# ESP32_School_Prototype.net
KiCad netlist of a schematic drawn in EAGLE
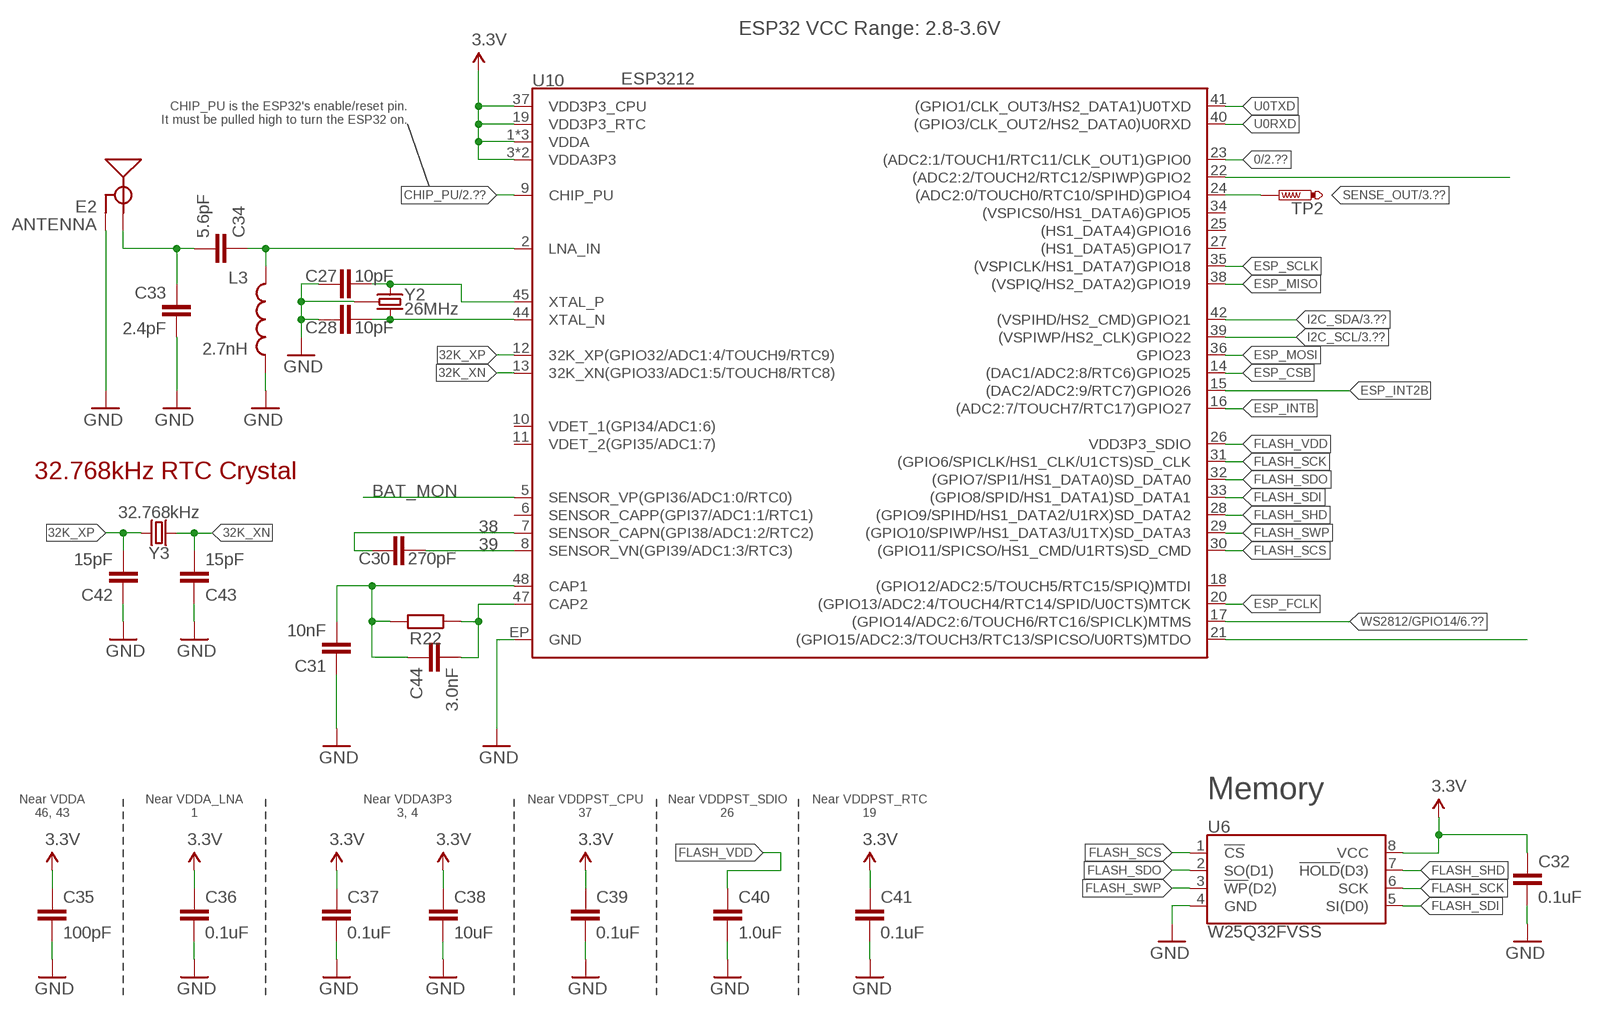
[diagram p0: schematic, sheet 1]
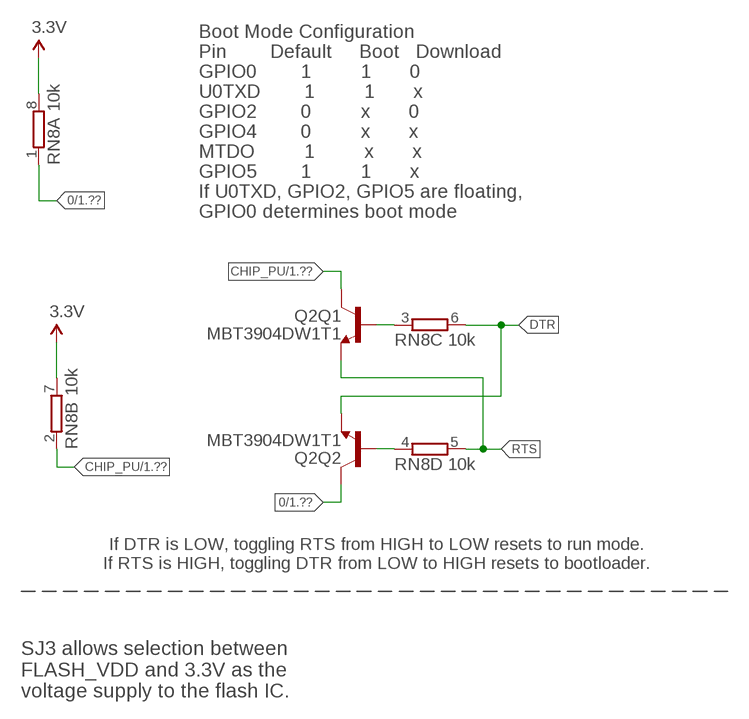
[diagram p1: schematic, sheet 2]
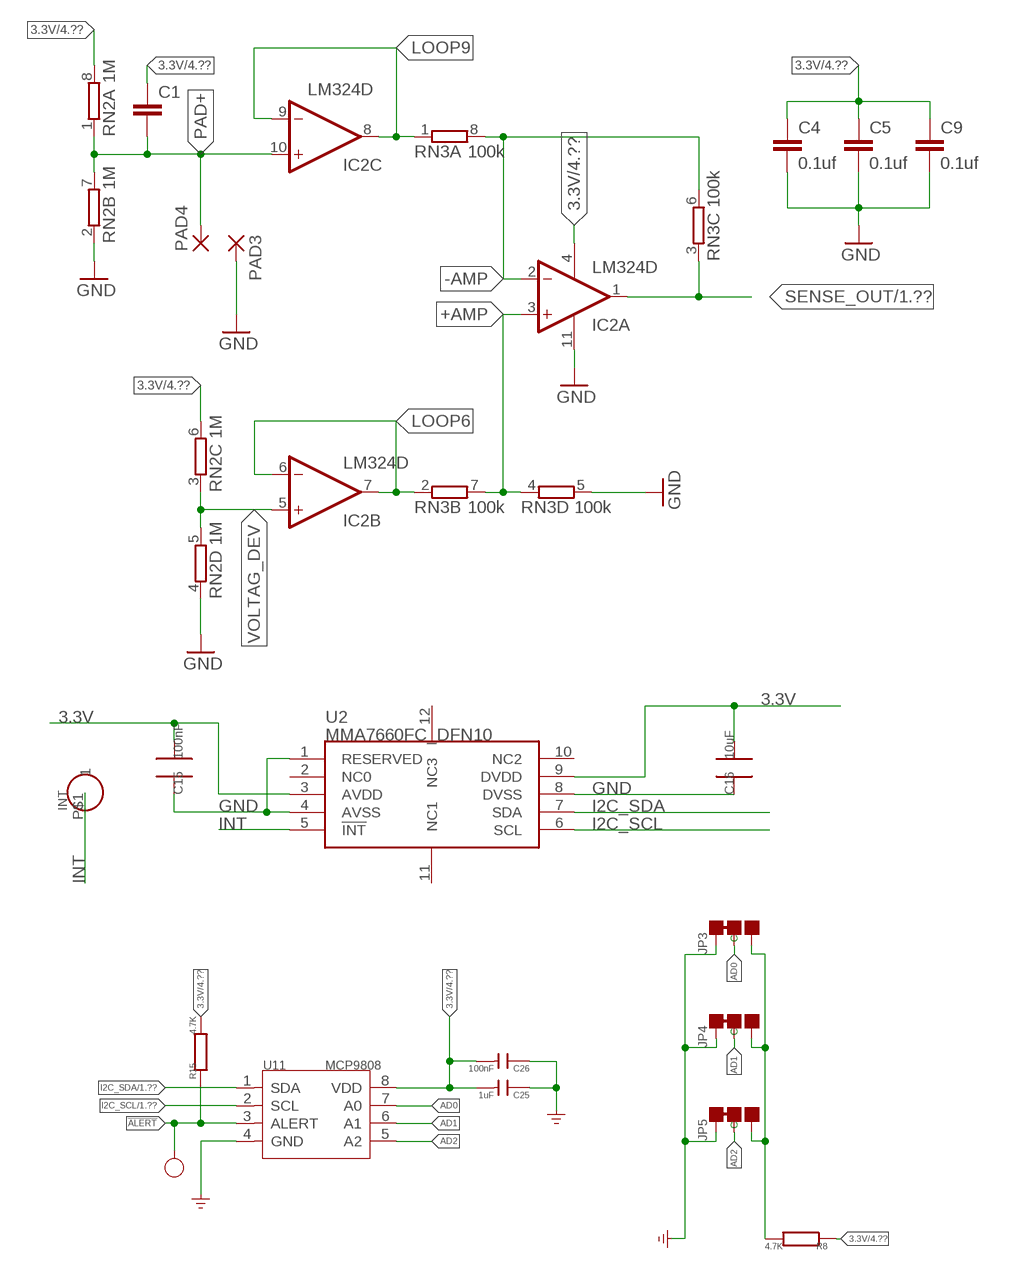
[diagram p2: schematic, sheet 3]
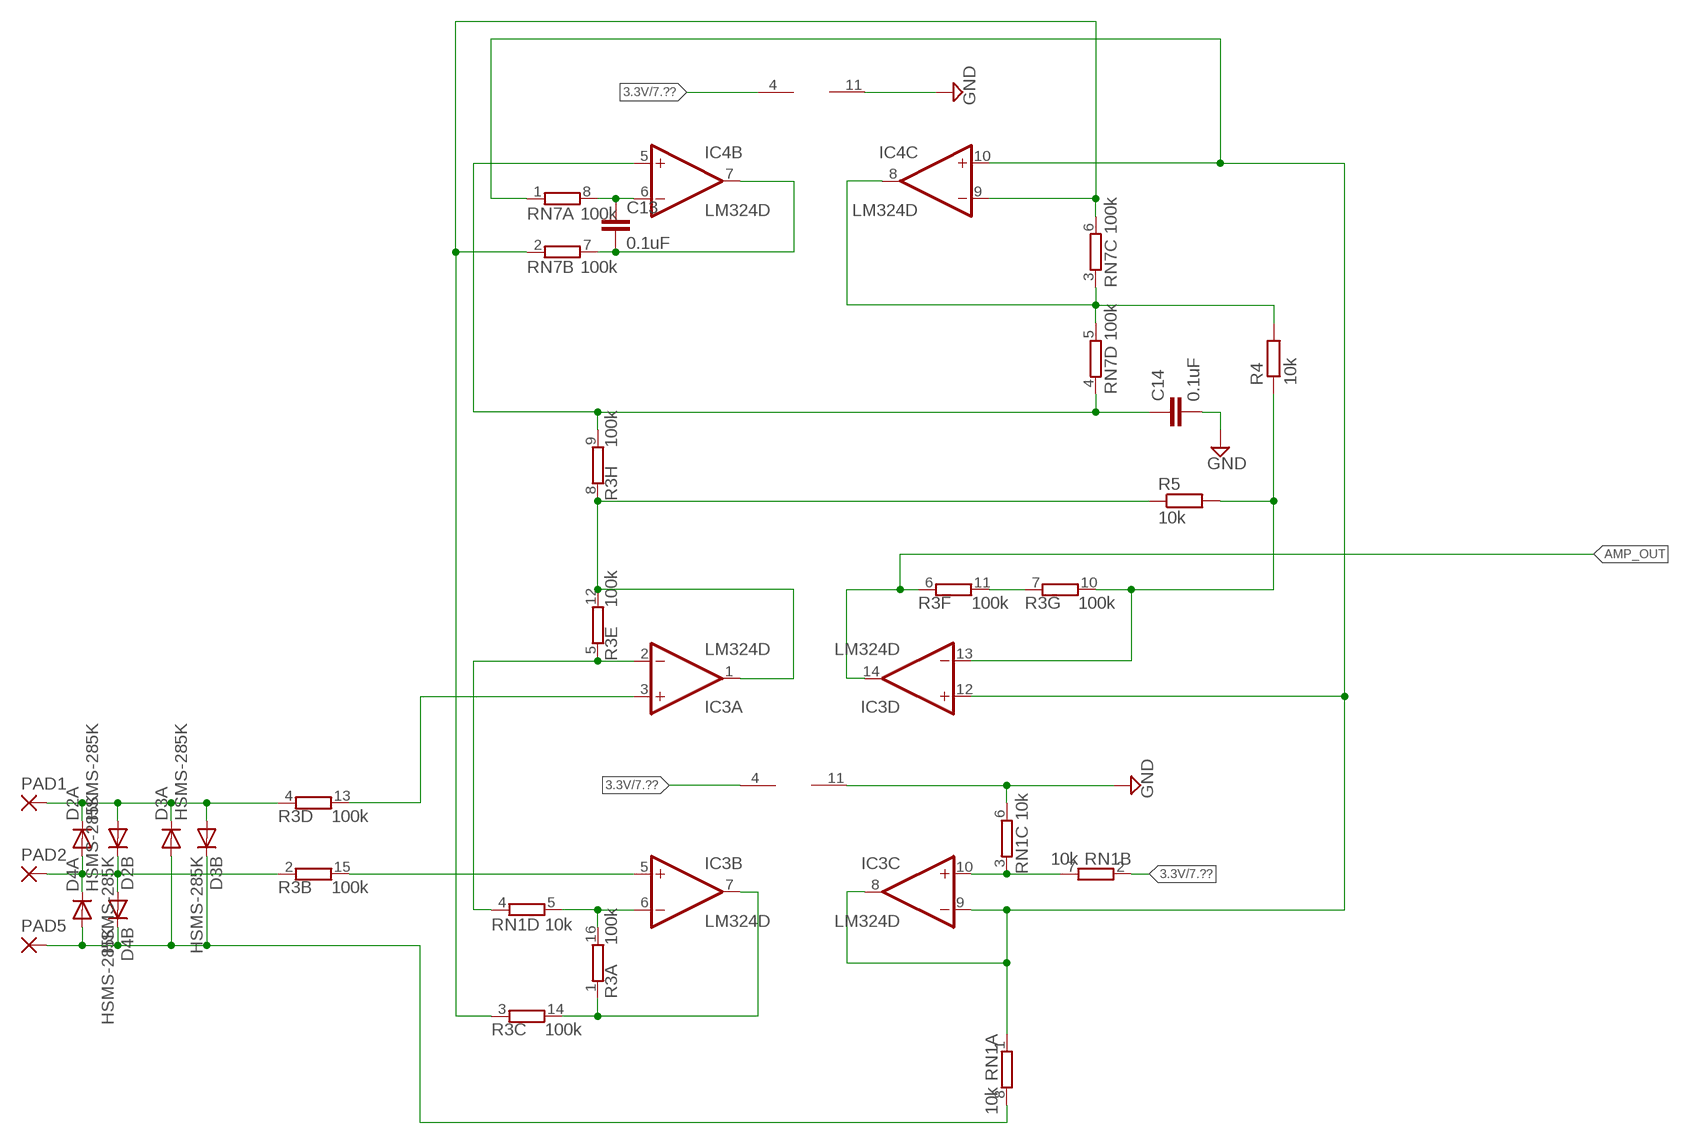
[diagram p3: schematic, sheet 4]
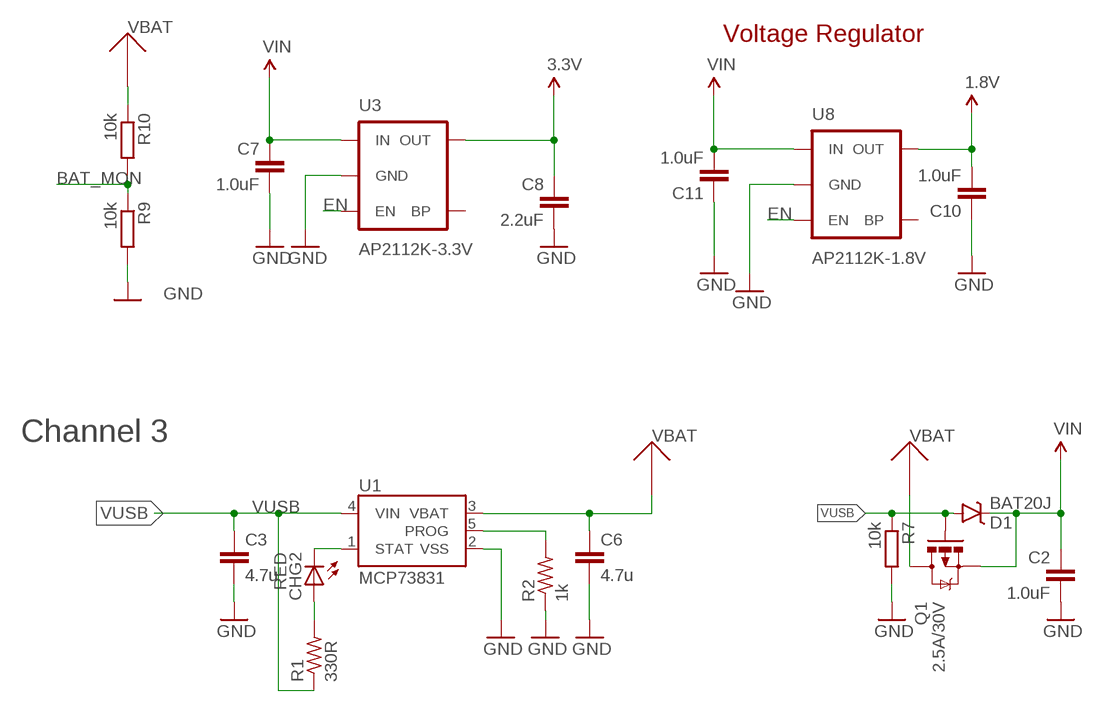
[diagram p4: schematic, sheet 5]
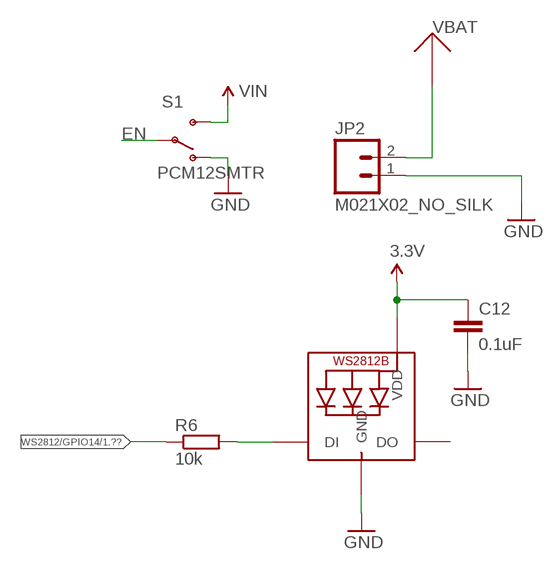
[diagram p5: schematic, sheet 6]
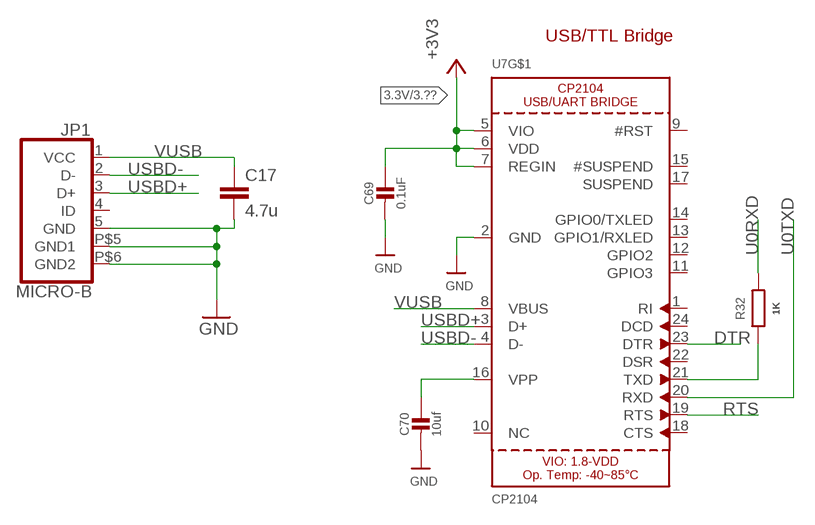
[diagram p6: schematic, sheet 7]
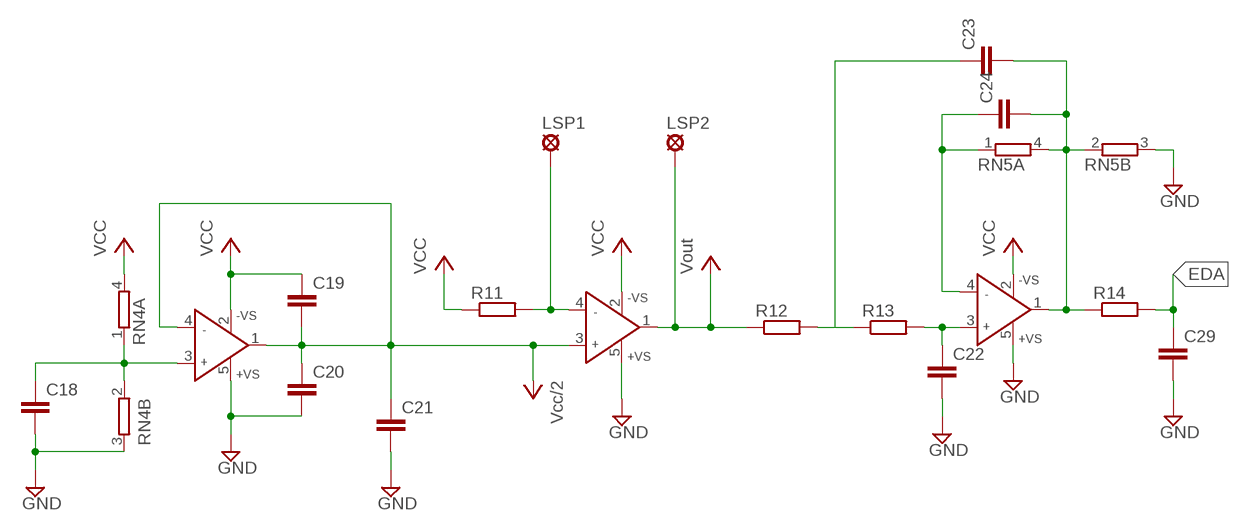
[diagram p7: schematic, sheet 8]

(export (version "E")
  (design (tool "Eeschema 10.0.6"))
  (components
    (comp (ref "C1")
      (value "C-EUC0603K")
      (footprint "eagle-import:C0603K")
      (libsource (lib "eagle-import") (part "rcl_334_C-EUC0603K"))
    )
    (comp (ref "C4")
      (value "0.1uf")
      (footprint "eagle-import:C0603K")
      (libsource (lib "eagle-import") (part "rcl_334_C-EUC0603K"))
    )
    (comp (ref "C5")
      (value "0.1uf")
      (footprint "eagle-import:C0603K")
      (libsource (lib "eagle-import") (part "rcl_334_C-EUC0603K"))
    )
    (comp (ref "C9")
      (value "0.1uf")
      (footprint "eagle-import:C0603K")
      (libsource (lib "eagle-import") (part "rcl_334_C-EUC0603K"))
    )
    (comp (ref "C15")
      (value "100nF")
      (footprint "eagle-import:0603_S")
      (libsource (lib "eagle-import") (part "C0603_S"))
    )
    (comp (ref "C16")
      (value "10uF")
      (footprint "eagle-import:0805_S")
      (libsource (lib "eagle-import") (part "C0805_S"))
    )
    (comp (ref "C25")
      (value "1uF")
      (footprint "eagle-import:C0603")
      (libsource (lib "eagle-import") (part "C-0603"))
    )
    (comp (ref "C26")
      (value "100nF")
      (footprint "eagle-import:C0603")
      (libsource (lib "eagle-import") (part "C-0603"))
    )
    (comp (ref "GND16")
      (value "TEST-POINT'4545'")
      (footprint "eagle-import:TP-D45MIL")
      (fields (field (name "PARTNO") "DNP"))
      (libsource (lib "eagle-import") (part "TEST-POINT'4545'"))
    )
    (comp (ref "IC2")
      (value "LM324D")
      (footprint "eagle-import:SO14")
      (libsource (lib "eagle-import") (part "LM324D"))
    )
    (comp (ref "INT")
      (value "HEADER-1P-35")
      (footprint "eagle-import:1P-65_35MIL")
      (libsource (lib "eagle-import") (part "HEADER-1P-35"))
    )
    (comp (ref "JP3")
      (value "JP-3P-SHORT")
      (footprint "eagle-import:3P-SMD-SHORT")
      (libsource (lib "eagle-import") (part "JP-3P-SHORT"))
    )
    (comp (ref "JP4")
      (value "JP-3P-SHORT")
      (footprint "eagle-import:3P-SMD-SHORT")
      (libsource (lib "eagle-import") (part "JP-3P-SHORT"))
    )
    (comp (ref "JP5")
      (value "JP-3P-SHORT")
      (footprint "eagle-import:3P-SMD-SHORT")
      (libsource (lib "eagle-import") (part "JP-3P-SHORT"))
    )
    (comp (ref "PAD3")
      (value "2,54/1,1")
      (footprint "eagle-import:2,54_1,1")
      (libsource (lib "eagle-import") (part "2,54/1,1"))
    )
    (comp (ref "PAD4")
      (value "2,54/1,1")
      (footprint "eagle-import:2,54_1,1")
      (libsource (lib "eagle-import") (part "2,54/1,1"))
    )
    (comp (ref "R8")
      (value "4.7K")
      (footprint "eagle-import:R0402")
      (libsource (lib "eagle-import") (part "resistor_348_R-EU_R0402"))
    )
    (comp (ref "R15")
      (value "4.7K")
      (footprint "eagle-import:R0402")
      (libsource (lib "eagle-import") (part "resistor_348_R-EU_R0402"))
    )
    (comp (ref "RN2")
      (value "1M")
      (footprint "eagle-import:0603-ARV")
      (libsource (lib "eagle-import") (part "4R-N0603-ARV"))
    )
    (comp (ref "RN3")
      (value "100k")
      (footprint "eagle-import:0603-ARV")
      (libsource (lib "eagle-import") (part "4R-N0603-ARV"))
    )
    (comp (ref "U2")
      (value "MMA7660FC_DFN10")
      (footprint "eagle-import:DFN10")
      (libsource (lib "eagle-import") (part "MMA7660FC_DFN10"))
    )
    (comp (ref "U11")
      (value "MCP9808")
      (footprint "eagle-import:MSOP8-0.65-3X3X0.85MM")
      (libsource (lib "eagle-import") (part "SENSOR-MCP9808"))
    )
    (comp (ref "C17")
      (value "4.7u")
      (footprint "eagle-import:C0805")
      (libsource (lib "eagle-import") (part "C-EUC0805"))
    )
    (comp (ref "C69")
      (value "0.1uF")
      (footprint "eagle-import:_0402")
      (libsource (lib "eagle-import") (part "CAP_CERAMIC_0402"))
    )
    (comp (ref "C70")
      (value "10uf")
      (footprint "eagle-import:0805-NO")
      (libsource (lib "eagle-import") (part "CAP_CERAMIC0805-NOOUTLINE"))
    )
    (comp (ref "JP1")
      (value "MICRO-B")
      (footprint "eagle-import:MICRO-B")
      (libsource (lib "eagle-import") (part "MICRO-B"))
    )
    (comp (ref "R32")
      (value "1K")
      (footprint "eagle-import:R0402")
      (libsource (lib "eagle-import") (part "resistor_348_R-EU_R0402"))
    )
    (comp (ref "U7")
      (value "CP2104")
      (footprint "eagle-import:QFN24_4MM_SMSC")
      (libsource (lib "eagle-import") (part "CP2104"))
    )
    (comp (ref "Q2")
      (value "MBT3904DW1T1")
      (footprint "eagle-import:SC70-6")
      (libsource (lib "eagle-import") (part "MBT3904DW1T1"))
    )
    (comp (ref "RN8")
      (value "10k")
      (footprint "eagle-import:0603-ARC")
      (libsource (lib "eagle-import") (part "4R-N0603-ARC"))
    )
    (comp (ref "C13")
      (value "0.1uF")
      (footprint "eagle-import:0402")
      (libsource (lib "eagle-import") (part "SparkFun-Capacitors_510_0.1UF-0402-16V-10%"))
    )
    (comp (ref "C14")
      (value "0.1uF")
      (footprint "eagle-import:0402")
      (libsource (lib "eagle-import") (part "SparkFun-Capacitors_510_0.1UF-0402-16V-10%"))
    )
    (comp (ref "D2")
      (value "HSMS-285K")
      (footprint "eagle-import:SOT363")
      (libsource (lib "eagle-import") (part "HSMS-285K"))
    )
    (comp (ref "D3")
      (value "HSMS-285K")
      (footprint "eagle-import:SOT363")
      (libsource (lib "eagle-import") (part "HSMS-285K"))
    )
    (comp (ref "D4")
      (value "HSMS-285K")
      (footprint "eagle-import:SOT363")
      (libsource (lib "eagle-import") (part "HSMS-285K"))
    )
    (comp (ref "IC3")
      (value "LM324D")
      (footprint "eagle-import:SO14")
      (libsource (lib "eagle-import") (part "LM324D"))
    )
    (comp (ref "IC4")
      (value "LM324D")
      (footprint "eagle-import:SO14")
      (libsource (lib "eagle-import") (part "LM324D"))
    )
    (comp (ref "PAD1")
      (value "2,54/1,1")
      (footprint "eagle-import:2,54_1,1")
      (libsource (lib "eagle-import") (part "2,54/1,1"))
    )
    (comp (ref "PAD2")
      (value "2,54/1,1")
      (footprint "eagle-import:2,54_1,1")
      (libsource (lib "eagle-import") (part "2,54/1,1"))
    )
    (comp (ref "PAD5")
      (value "2,54/1,1")
      (footprint "eagle-import:2,54_1,1")
      (libsource (lib "eagle-import") (part "2,54/1,1"))
    )
    (comp (ref "R3")
      (value "100k")
      (footprint "eagle-import:EXB2HV")
      (libsource (lib "eagle-import") (part "8R-NEXB2HV"))
    )
    (comp (ref "R4")
      (value "10k")
      (footprint "eagle-import:R0603")
      (libsource (lib "eagle-import") (part "resistor_348_R-EU_R0603"))
    )
    (comp (ref "R5")
      (value "10k")
      (footprint "eagle-import:R0603")
      (libsource (lib "eagle-import") (part "resistor_348_R-EU_R0603"))
    )
    (comp (ref "RN1")
      (value "10k")
      (footprint "eagle-import:4X0402ARV341")
      (libsource (lib "eagle-import") (part "4R-N0402ARV341"))
    )
    (comp (ref "RN7")
      (value "100k")
      (footprint "eagle-import:4X0402ARV341")
      (libsource (lib "eagle-import") (part "4R-N0402ARV341"))
    )
    (comp (ref "C18")
      (value "C-EUC0201")
      (footprint "eagle-import:C0201")
      (libsource (lib "eagle-import") (part "resistor_348_C-EUC0201"))
    )
    (comp (ref "C19")
      (value "C-EUC0201")
      (footprint "eagle-import:C0201")
      (libsource (lib "eagle-import") (part "resistor_348_C-EUC0201"))
    )
    (comp (ref "C20")
      (value "C-EUC0201")
      (footprint "eagle-import:C0201")
      (libsource (lib "eagle-import") (part "resistor_348_C-EUC0201"))
    )
    (comp (ref "C21")
      (value "C-EUC0201")
      (footprint "eagle-import:C0201")
      (libsource (lib "eagle-import") (part "resistor_348_C-EUC0201"))
    )
    (comp (ref "C22")
      (value "C-EUC0201")
      (footprint "eagle-import:C0201")
      (libsource (lib "eagle-import") (part "resistor_348_C-EUC0201"))
    )
    (comp (ref "C23")
      (value "C-EUC0201")
      (footprint "eagle-import:C0201")
      (libsource (lib "eagle-import") (part "resistor_348_C-EUC0201"))
    )
    (comp (ref "C24")
      (value "C-EUC0201")
      (footprint "eagle-import:C0201")
      (libsource (lib "eagle-import") (part "resistor_348_C-EUC0201"))
    )
    (comp (ref "C29")
      (value "C-EUC0201")
      (footprint "eagle-import:C0201")
      (libsource (lib "eagle-import") (part "resistor_348_C-EUC0201"))
    )
    (comp (ref "IC1")
      (value "AD8603UJ")
      (footprint "eagle-import:SOT23-5")
      (fields (field (name "MF") "ALTERA CORPORATION") (field (name "MPN") "AD8603AUJZ-REEL7"))
      (libsource (lib "eagle-import") (part "AD8603UJ"))
    )
    (comp (ref "IC5")
      (value "AD8603UJ")
      (footprint "eagle-import:SOT23-5")
      (fields (field (name "MF") "ALTERA CORPORATION") (field (name "MPN") "AD8603AUJZ-REEL7"))
      (libsource (lib "eagle-import") (part "AD8603UJ"))
    )
    (comp (ref "IC6")
      (value "AD8603UJ")
      (footprint "eagle-import:SOT23-5")
      (fields (field (name "MF") "ALTERA CORPORATION") (field (name "MPN") "AD8603AUJZ-REEL7"))
      (libsource (lib "eagle-import") (part "AD8603UJ"))
    )
    (comp (ref "LSP1")
      (value "MCS08")
      (footprint "eagle-import:MCS08")
      (libsource (lib "eagle-import") (part "MCS08"))
    )
    (comp (ref "LSP2")
      (value "MCS08")
      (footprint "eagle-import:MCS08")
      (libsource (lib "eagle-import") (part "MCS08"))
    )
    (comp (ref "R11")
      (value "R-EU_M2012")
      (footprint "eagle-import:M2012")
      (libsource (lib "eagle-import") (part "R-EU_M2012"))
    )
    (comp (ref "R12")
      (value "R-EU_M2012")
      (footprint "eagle-import:M2012")
      (libsource (lib "eagle-import") (part "R-EU_M2012"))
    )
    (comp (ref "R13")
      (value "R-EU_M2012")
      (footprint "eagle-import:M2012")
      (libsource (lib "eagle-import") (part "R-EU_M2012"))
    )
    (comp (ref "R14")
      (value "R-EU_M2012")
      (footprint "eagle-import:M2012")
      (libsource (lib "eagle-import") (part "R-EU_M2012"))
    )
    (comp (ref "RN4")
      (value "2R-NEXBV4V")
      (footprint "eagle-import:EXBV4V")
      (libsource (lib "eagle-import") (part "2R-NEXBV4V"))
    )
    (comp (ref "RN5")
      (value "2R-NEXBV4V")
      (footprint "eagle-import:EXBV4V")
      (libsource (lib "eagle-import") (part "2R-NEXBV4V"))
    )
    (comp (ref "C2")
      (value "1.0uF")
      (footprint "eagle-import:C0402")
      (libsource (lib "eagle-import") (part "C-EUC0402"))
    )
    (comp (ref "C3")
      (value "4.7u")
      (footprint "eagle-import:C0805")
      (libsource (lib "eagle-import") (part "C-EUC0805"))
    )
    (comp (ref "C6")
      (value "4.7u")
      (footprint "eagle-import:C0805")
      (libsource (lib "eagle-import") (part "C-EUC0805"))
    )
    (comp (ref "C7")
      (value "1.0uF")
      (footprint "eagle-import:0805")
      (libsource (lib "eagle-import") (part "1.0UF-25V-+80/-20(0805)"))
    )
    (comp (ref "C8")
      (value "2.2uF")
      (footprint "eagle-import:C0805")
      (libsource (lib "eagle-import") (part "C-EUC0805"))
    )
    (comp (ref "C10")
      (value "1.0uF")
      (footprint "eagle-import:C0805")
      (libsource (lib "eagle-import") (part "C-EUC0805"))
    )
    (comp (ref "C11")
      (value "1.0uF")
      (footprint "eagle-import:C0805")
      (libsource (lib "eagle-import") (part "C-EUC0805"))
    )
    (comp (ref "CHG2")
      (value "RED")
      (footprint "eagle-import:CHIPLED_0603")
      (libsource (lib "eagle-import") (part "LEDCHIPLED_0603"))
    )
    (comp (ref "D1")
      (value "BAT20J")
      (footprint "eagle-import:SOD-323")
      (libsource (lib "eagle-import") (part "DIODE-SCHOTTKY-BAT20J"))
    )
    (comp (ref "Q1")
      (value "2.5A/30V")
      (footprint "eagle-import:SOT23-3")
      (libsource (lib "eagle-import") (part "MOSFET-PCHANNELDMG2307L"))
    )
    (comp (ref "R1")
      (value "330R")
      (footprint "eagle-import:R0402")
      (libsource (lib "eagle-import") (part "R-US_R0402"))
    )
    (comp (ref "R2")
      (value "1k")
      (footprint "eagle-import:R0402")
      (libsource (lib "eagle-import") (part "R-US_R0402"))
    )
    (comp (ref "R7")
      (value "10k")
      (footprint "eagle-import:R0402")
      (libsource (lib "eagle-import") (part "resistor_348_R-EU_R0402"))
    )
    (comp (ref "R9")
      (value "10k")
      (footprint "eagle-import:R0402")
      (libsource (lib "eagle-import") (part "resistor_348_R-EU_R0402"))
    )
    (comp (ref "R10")
      (value "10k")
      (footprint "eagle-import:R0402")
      (libsource (lib "eagle-import") (part "resistor_348_R-EU_R0402"))
    )
    (comp (ref "U1")
      (value "MCP73831")
      (footprint "eagle-import:SOT23-5")
      (libsource (lib "eagle-import") (part "MCP73831"))
    )
    (comp (ref "U3")
      (value "AP2112K-3.3V")
      (footprint "eagle-import:SOT23-5")
      (libsource (lib "eagle-import") (part "V_REG_LDOSMD"))
    )
    (comp (ref "U8")
      (value "AP2112K-1.8V")
      (footprint "eagle-import:SOT23-5")
      (libsource (lib "eagle-import") (part "V_REG_LDOSMD"))
    )
    (comp (ref "C27")
      (value "10pF")
      (footprint "eagle-import:0603")
      (libsource (lib "eagle-import") (part "10PF-0603-50V-5%"))
    )
    (comp (ref "C28")
      (value "10pF")
      (footprint "eagle-import:0603")
      (libsource (lib "eagle-import") (part "10PF-0603-50V-5%"))
    )
    (comp (ref "C30")
      (value "270pF")
      (footprint "eagle-import:0603")
      (libsource (lib "eagle-import") (part "270PF-50V-5%(0603)"))
    )
    (comp (ref "C31")
      (value "10nF")
      (footprint "eagle-import:0603")
      (libsource (lib "eagle-import") (part "10NF-0603-50V-10%"))
    )
    (comp (ref "C32")
      (value "0.1uF")
      (footprint "eagle-import:0402")
      (libsource (lib "eagle-import") (part "0.1UF-0402-16V-10%"))
    )
    (comp (ref "C33")
      (value "2.4pF")
      (footprint "eagle-import:0603")
      (libsource (lib "eagle-import") (part "2.4PF-0603-50V-5%"))
    )
    (comp (ref "C34")
      (value "5.6pF")
      (footprint "eagle-import:0603")
      (libsource (lib "eagle-import") (part "5.6PF-50V-5%(0603)"))
    )
    (comp (ref "C35")
      (value "100pF")
      (footprint "eagle-import:0603")
      (libsource (lib "eagle-import") (part "100PF-0603-50V-5%"))
    )
    (comp (ref "C36")
      (value "0.1uF")
      (footprint "eagle-import:0603")
      (libsource (lib "eagle-import") (part "0.1UF-0603-25V-(+80/-20%)"))
    )
    (comp (ref "C37")
      (value "0.1uF")
      (footprint "eagle-import:0603")
      (libsource (lib "eagle-import") (part "0.1UF-0603-25V-(+80/-20%)"))
    )
    (comp (ref "C38")
      (value "10uF")
      (footprint "eagle-import:0603")
      (libsource (lib "eagle-import") (part "10UF-0603-6.3V-20%"))
    )
    (comp (ref "C39")
      (value "0.1uF")
      (footprint "eagle-import:0402")
      (libsource (lib "eagle-import") (part "0.1UF-0402-16V-10%"))
    )
    (comp (ref "C40")
      (value "1.0uF")
      (footprint "eagle-import:0603")
      (libsource (lib "eagle-import") (part "1.0UF-0603-16V-10%"))
    )
    (comp (ref "C41")
      (value "0.1uF")
      (footprint "eagle-import:0603")
      (libsource (lib "eagle-import") (part "0.1UF-0603-25V-(+80/-20%)"))
    )
    (comp (ref "C42")
      (value "15pF")
      (footprint "eagle-import:0603")
      (libsource (lib "eagle-import") (part "15PF-0603-50V-5%"))
    )
    (comp (ref "C43")
      (value "15pF")
      (footprint "eagle-import:0603")
      (libsource (lib "eagle-import") (part "15PF-0603-50V-5%"))
    )
    (comp (ref "C44")
      (value "3.0nF")
      (footprint "eagle-import:0603")
      (libsource (lib "eagle-import") (part "3.0NF-0603-50V-5%"))
    )
    (comp (ref "E2")
      (value "ANTENNA")
      (footprint "eagle-import:TRACE_ANTENNA_2.4GHZ_25.7MM_TUNED")
      (libsource (lib "eagle-import") (part "ANTENNATRACE-TUNED"))
    )
    (comp (ref "L3")
      (value "2.7nH")
      (footprint "eagle-import:0603")
      (libsource (lib "eagle-import") (part "INDUCTOR0603"))
    )
    (comp (ref "R22")
      (value "20k")
      (footprint "eagle-import:R0402")
      (libsource (lib "eagle-import") (part "resistor_348_R-EU_R0402"))
    )
    (comp (ref "TP2")
      (value "PTR1TP10SQ")
      (footprint "eagle-import:TP10SQ")
      (libsource (lib "eagle-import") (part "PTR1TP10SQ"))
    )
    (comp (ref "U6")
      (value "W25Q32FVSS")
      (footprint "eagle-import:SOIC-8")
      (libsource (lib "eagle-import") (part "W25Q32FVSS"))
    )
    (comp (ref "U10")
      (value "ESP3212")
      (footprint "eagle-import:QFN48-0.4MM")
      (libsource (lib "eagle-import") (part "ESP3212"))
    )
    (comp (ref "Y2")
      (value "26MHz")
      (footprint "eagle-import:CRYSTAL-SMD-3.2X2.5")
      (libsource (lib "eagle-import") (part "CRYSTAL-GROUNDED3.2X2.5"))
    )
    (comp (ref "Y3")
      (value "32.768kHz")
      (footprint "eagle-import:CRYSTAL-SMD-3.2X1.5MM")
      (libsource (lib "eagle-import") (part "CRYSTAL-32.768KHZSMD-3.2X1.5"))
    )
    (comp (ref "C12")
      (value "0.1uF")
      (footprint "eagle-import:0603")
      (libsource (lib "eagle-import") (part "0.1UF-0603-25V-(+80/-20%)"))
    )
    (comp (ref "JP2")
      (value "M021X02_NO_SILK")
      (footprint "eagle-import:1X02_NO_SILK")
      (libsource (lib "eagle-import") (part "M021X02_NO_SILK"))
    )
    (comp (ref "LED2")
      (value "WS2812B5050")
      (footprint "eagle-import:WS2812B")
      (libsource (lib "eagle-import") (part "WS2812B5050"))
    )
    (comp (ref "R6")
      (value "10k")
      (footprint "eagle-import:R0402")
      (libsource (lib "eagle-import") (part "resistor_348_R-EU_R0402"))
    )
    (comp (ref "S1")
      (value "PCM12SMTR")
      (footprint "eagle-import:SWITCH-SPST-SMD-A")
      (libsource (lib "eagle-import") (part "SWITCH-SPDT-SMD-A"))
    )
  )
  (nets
    (net (code "1") (name "+AMP") (class "Default")
      (node (ref "IC2") (pin "3") (pinfunction "+IN_3") (pintype "input"))
      (node (ref "RN3") (pin "4") (pinfunction "1_4") (pintype "passive"))
      (node (ref "RN3") (pin "7") (pinfunction "2_7") (pintype "passive"))
    )
    (net (code "2") (name "-AMP") (class "Default")
      (node (ref "IC2") (pin "2") (pinfunction "-IN_2") (pintype "input"))
      (node (ref "RN3") (pin "6") (pinfunction "2_6") (pintype "passive"))
      (node (ref "RN3") (pin "8") (pinfunction "2_8") (pintype "passive"))
    )
    (net (code "3") (name "0") (class "Default")
      (node (ref "Q2") (pin "6") (pinfunction "C_6") (pintype "passive"))
      (node (ref "RN8") (pin "1") (pinfunction "1_1") (pintype "passive"))
      (node (ref "U10") (pin "23") (pinfunction "(ADC2:1/TOUCH1/RTC11/CLK_OUT1)GPIO0_23") (pintype "bidirectional"))
    )
    (net (code "4") (name "1.8V") (class "Default")
      (node (ref "C10") (pin "2") (pinfunction "2_2") (pintype "passive"))
      (node (ref "U8") (pin "5") (pinfunction "OUT_5") (pintype "passive"))
    )
    (net (code "5") (name "3.3V") (class "Default")
      (node (ref "C1") (pin "1") (pinfunction "1_1") (pintype "passive"))
      (node (ref "C12") (pin "1") (pinfunction "1_1") (pintype "passive"))
      (node (ref "C15") (pin "2") (pinfunction "2_2") (pintype "bidirectional"))
      (node (ref "C16") (pin "2") (pinfunction "2_2") (pintype "bidirectional"))
      (node (ref "C25") (pin "2") (pinfunction "2_2") (pintype "passive"))
      (node (ref "C26") (pin "2") (pinfunction "2_2") (pintype "passive"))
      (node (ref "C32") (pin "1") (pinfunction "1_1") (pintype "passive"))
      (node (ref "C35") (pin "1") (pinfunction "1_1") (pintype "passive"))
      (node (ref "C36") (pin "1") (pinfunction "1_1") (pintype "passive"))
      (node (ref "C37") (pin "1") (pinfunction "1_1") (pintype "passive"))
      (node (ref "C38") (pin "1") (pinfunction "1_1") (pintype "passive"))
      (node (ref "C39") (pin "1") (pinfunction "1_1") (pintype "passive"))
      (node (ref "C4") (pin "1") (pinfunction "1_1") (pintype "passive"))
      (node (ref "C41") (pin "1") (pinfunction "1_1") (pintype "passive"))
      (node (ref "C5") (pin "1") (pinfunction "1_1") (pintype "passive"))
      (node (ref "C69") (pin "1") (pinfunction "1_1") (pintype "passive"))
      (node (ref "C8") (pin "1") (pinfunction "1_1") (pintype "passive"))
      (node (ref "C9") (pin "1") (pinfunction "1_1") (pintype "passive"))
      (node (ref "IC2") (pin "4") (pinfunction "V+_4") (pintype "power_in"))
      (node (ref "IC3") (pin "4") (pinfunction "V+_4") (pintype "power_in"))
      (node (ref "IC4") (pin "4") (pinfunction "V+_4") (pintype "power_in"))
      (node (ref "LED2") (pin "1-VDD") (pinfunction "VDD_1-VDD") (pintype "power_in"))
      (node (ref "R15") (pin "2") (pinfunction "2_2") (pintype "passive"))
      (node (ref "R8") (pin "1") (pinfunction "1_1") (pintype "passive"))
      (node (ref "RN1") (pin "2") (pinfunction "1_2") (pintype "passive"))
      (node (ref "RN2") (pin "6") (pinfunction "2_6") (pintype "passive"))
      (node (ref "RN2") (pin "8") (pinfunction "2_8") (pintype "passive"))
      (node (ref "RN8") (pin "7") (pinfunction "2_7") (pintype "passive"))
      (node (ref "RN8") (pin "8") (pinfunction "2_8") (pintype "passive"))
      (node (ref "U10") (pin "1") (pinfunction "VDDA_1") (pintype "bidirectional"))
      (node (ref "U10") (pin "19") (pinfunction "VDD3P3_RTC_19") (pintype "bidirectional"))
      (node (ref "U10") (pin "3") (pinfunction "VDDA3P3_3") (pintype "bidirectional"))
      (node (ref "U10") (pin "37") (pinfunction "VDD3P3_CPU_37") (pintype "bidirectional"))
      (node (ref "U10") (pin "4") (pinfunction "VDDA3P3_4") (pintype "bidirectional"))
      (node (ref "U10") (pin "43") (pinfunction "VDDA_43") (pintype "bidirectional"))
      (node (ref "U10") (pin "46") (pinfunction "VDDA_46") (pintype "bidirectional"))
      (node (ref "U11") (pin "8") (pinfunction "VDD_8") (pintype "bidirectional"))
      (node (ref "U2") (pin "3") (pinfunction "AVDD_3") (pintype "bidirectional"))
      (node (ref "U2") (pin "9") (pinfunction "DVDD_9") (pintype "bidirectional"))
      (node (ref "U3") (pin "5") (pinfunction "OUT_5") (pintype "passive"))
      (node (ref "U6") (pin "8") (pinfunction "VCC_8") (pintype "bidirectional"))
      (node (ref "U7") (pin "5") (pinfunction "VIO_5") (pintype "power_in"))
      (node (ref "U7") (pin "6") (pinfunction "VDD_6") (pintype "power_in"))
      (node (ref "U7") (pin "7") (pinfunction "REGIN_7") (pintype "power_in"))
    )
    (net (code "6") (name "32K_XN") (class "Default")
      (node (ref "C43") (pin "2") (pinfunction "2_2") (pintype "passive"))
      (node (ref "U10") (pin "13") (pinfunction "32K_XN(GPIO33/ADC1:5/TOUCH8/RTC8)_13") (pintype "bidirectional"))
      (node (ref "Y3") (pin "P$2") (pinfunction "2_P$2") (pintype "passive"))
    )
    (net (code "7") (name "32K_XP") (class "Default")
      (node (ref "C42") (pin "2") (pinfunction "2_2") (pintype "passive"))
      (node (ref "U10") (pin "12") (pinfunction "32K_XP(GPIO32/ADC1:4/TOUCH9/RTC9)_12") (pintype "bidirectional"))
      (node (ref "Y3") (pin "P$1") (pinfunction "1_P$1") (pintype "passive"))
    )
    (net (code "8") (name "38") (class "Default")
      (node (ref "C30") (pin "1") (pinfunction "1_1") (pintype "passive"))
      (node (ref "U10") (pin "7") (pinfunction "SENSOR_CAPN(GPI38/ADC1:2/RTC2)_7") (pintype "bidirectional"))
    )
    (net (code "9") (name "39") (class "Default")
      (node (ref "C30") (pin "2") (pinfunction "2_2") (pintype "passive"))
      (node (ref "U10") (pin "8") (pinfunction "SENSOR_VN(GPI39/ADC1:3/RTC3)_8") (pintype "bidirectional"))
    )
    (net (code "10") (name "AD0") (class "Default")
      (node (ref "JP3") (pin "MM") (pinfunction "C_MM") (pintype "bidirectional"))
      (node (ref "U11") (pin "7") (pinfunction "A0_7") (pintype "bidirectional"))
    )
    (net (code "11") (name "AD1") (class "Default")
      (node (ref "JP4") (pin "MM") (pinfunction "C_MM") (pintype "bidirectional"))
      (node (ref "U11") (pin "6") (pinfunction "A1_6") (pintype "bidirectional"))
    )
    (net (code "12") (name "AD2") (class "Default")
      (node (ref "JP5") (pin "MM") (pinfunction "C_MM") (pintype "bidirectional"))
      (node (ref "U11") (pin "5") (pinfunction "A2_5") (pintype "bidirectional"))
    )
    (net (code "13") (name "AMP_OUT") (class "Default")
      (node (ref "IC3") (pin "14") (pinfunction "OUT_14") (pintype "output"))
      (node (ref "R3") (pin "6") (pinfunction "1_6") (pintype "passive"))
    )
    (net (code "14") (name "BAT_MON") (class "Default")
      (node (ref "R10") (pin "2") (pinfunction "2_2") (pintype "passive"))
      (node (ref "R9") (pin "1") (pinfunction "1_1") (pintype "passive"))
      (node (ref "U10") (pin "5") (pinfunction "SENSOR_VP(GPI36/ADC1:0/RTC0)_5") (pintype "bidirectional"))
    )
    (net (code "15") (name "CHIP_PU") (class "Default")
      (node (ref "Q2") (pin "3") (pinfunction "C_3") (pintype "passive"))
      (node (ref "RN8") (pin "2") (pinfunction "1_2") (pintype "passive"))
      (node (ref "U10") (pin "9") (pinfunction "CHIP_PU_9") (pintype "bidirectional"))
    )
    (net (code "16") (name "DTR") (class "Default")
      (node (ref "Q2") (pin "1") (pinfunction "E_1") (pintype "passive"))
      (node (ref "RN8") (pin "6") (pinfunction "2_6") (pintype "passive"))
      (node (ref "U7") (pin "23") (pinfunction "DTR_23") (pintype "output"))
    )
    (net (code "17") (name "EDA") (class "Default")
      (node (ref "C29") (pin "1") (pinfunction "1_1") (pintype "passive"))
      (node (ref "R14") (pin "2") (pinfunction "2_2") (pintype "passive"))
    )
    (net (code "18") (name "EN") (class "Default")
      (node (ref "S1") (pin "2") (pinfunction "P_2") (pintype "passive"))
      (node (ref "U3") (pin "3") (pinfunction "EN_3") (pintype "input"))
      (node (ref "U8") (pin "3") (pinfunction "EN_3") (pintype "input"))
    )
    (net (code "19") (name "ESP_CSB") (class "Default")
      (node (ref "U10") (pin "14") (pinfunction "(DAC1/ADC2:8/RTC6)GPIO25_14") (pintype "bidirectional"))
    )
    (net (code "20") (name "ESP_FCLK") (class "Default")
      (node (ref "U10") (pin "20") (pinfunction "(GPIO13/ADC2:4/TOUCH4/RTC14/SPID/U0CTS)MTCK_20") (pintype "bidirectional"))
    )
    (net (code "21") (name "ESP_INT2B") (class "Default")
      (node (ref "U10") (pin "15") (pinfunction "(DAC2/ADC2:9/RTC7)GPIO26_15") (pintype "bidirectional"))
    )
    (net (code "22") (name "ESP_INTB") (class "Default")
      (node (ref "U10") (pin "16") (pinfunction "(ADC2:7/TOUCH7/RTC17)GPIO27_16") (pintype "bidirectional"))
    )
    (net (code "23") (name "ESP_MISO") (class "Default")
      (node (ref "U10") (pin "38") (pinfunction "(VSPIQ/HS2_DATA2)GPIO19_38") (pintype "bidirectional"))
    )
    (net (code "24") (name "ESP_MOSI") (class "Default")
      (node (ref "U10") (pin "36") (pinfunction "GPIO23_36") (pintype "bidirectional"))
    )
    (net (code "25") (name "ESP_SCLK") (class "Default")
      (node (ref "U10") (pin "35") (pinfunction "(VSPICLK/HS1_DATA7)GPIO18_35") (pintype "bidirectional"))
    )
    (net (code "26") (name "FLASH_SCK") (class "Default")
      (node (ref "U10") (pin "31") (pinfunction "(GPIO6/SPICLK/HS1_CLK/U1CTS)SD_CLK_31") (pintype "bidirectional"))
      (node (ref "U6") (pin "6") (pinfunction "SCK_6") (pintype "bidirectional"))
    )
    (net (code "27") (name "FLASH_SCS") (class "Default")
      (node (ref "U10") (pin "30") (pinfunction "(GPIO11/SPICSO/HS1_CMD/U1RTS)SD_CMD_30") (pintype "bidirectional"))
      (node (ref "U6") (pin "1") (pinfunction "~{CS}_1") (pintype "bidirectional"))
    )
    (net (code "28") (name "FLASH_SDI") (class "Default")
      (node (ref "U10") (pin "33") (pinfunction "(GPIO8/SPID/HS1_DATA1)SD_DATA1_33") (pintype "bidirectional"))
      (node (ref "U6") (pin "5") (pinfunction "SI(D0)_5") (pintype "bidirectional"))
    )
    (net (code "29") (name "FLASH_SDO") (class "Default")
      (node (ref "U10") (pin "32") (pinfunction "(GPIO7/SPI1/HS1_DATA0)SD_DATA0_32") (pintype "bidirectional"))
      (node (ref "U6") (pin "2") (pinfunction "SO(D1)_2") (pintype "bidirectional"))
    )
    (net (code "30") (name "FLASH_SHD") (class "Default")
      (node (ref "U10") (pin "28") (pinfunction "(GPIO9/SPIHD/HS1_DATA2/U1RX)SD_DATA2_28") (pintype "bidirectional"))
      (node (ref "U6") (pin "7") (pinfunction "~{HOLD}(D3)_7") (pintype "bidirectional"))
    )
    (net (code "31") (name "FLASH_SWP") (class "Default")
      (node (ref "U10") (pin "29") (pinfunction "(GPIO10/SPIWP/HS1_DATA3/U1TX)SD_DATA3_29") (pintype "bidirectional"))
      (node (ref "U6") (pin "3") (pinfunction "~{WP}(D2)_3") (pintype "bidirectional"))
    )
    (net (code "32") (name "FLASH_VDD") (class "Default")
      (node (ref "C40") (pin "1") (pinfunction "1_1") (pintype "passive"))
      (node (ref "U10") (pin "26") (pinfunction "VDD3P3_SDIO_26") (pintype "bidirectional"))
    )
    (net (code "33") (name "GND") (class "Default")
      (node (ref "C10") (pin "1") (pinfunction "1_1") (pintype "passive"))
      (node (ref "C11") (pin "1") (pinfunction "1_1") (pintype "passive"))
      (node (ref "C12") (pin "2") (pinfunction "2_2") (pintype "passive"))
      (node (ref "C14") (pin "2") (pinfunction "2_2") (pintype "passive"))
      (node (ref "C15") (pin "1") (pinfunction "1_1") (pintype "bidirectional"))
      (node (ref "C16") (pin "1") (pinfunction "1_1") (pintype "bidirectional"))
      (node (ref "C17") (pin "2") (pinfunction "2_2") (pintype "passive"))
      (node (ref "C18") (pin "2") (pinfunction "2_2") (pintype "passive"))
      (node (ref "C2") (pin "2") (pinfunction "2_2") (pintype "passive"))
      (node (ref "C20") (pin "2") (pinfunction "2_2") (pintype "passive"))
      (node (ref "C21") (pin "2") (pinfunction "2_2") (pintype "passive"))
      (node (ref "C22") (pin "2") (pinfunction "2_2") (pintype "passive"))
      (node (ref "C25") (pin "1") (pinfunction "1_1") (pintype "passive"))
      (node (ref "C26") (pin "1") (pinfunction "1_1") (pintype "passive"))
      (node (ref "C27") (pin "1") (pinfunction "1_1") (pintype "passive"))
      (node (ref "C28") (pin "1") (pinfunction "1_1") (pintype "passive"))
      (node (ref "C29") (pin "2") (pinfunction "2_2") (pintype "passive"))
      (node (ref "C3") (pin "2") (pinfunction "2_2") (pintype "passive"))
      (node (ref "C31") (pin "1") (pinfunction "1_1") (pintype "passive"))
      (node (ref "C32") (pin "2") (pinfunction "2_2") (pintype "passive"))
      (node (ref "C33") (pin "2") (pinfunction "2_2") (pintype "passive"))
      (node (ref "C35") (pin "2") (pinfunction "2_2") (pintype "passive"))
      (node (ref "C36") (pin "2") (pinfunction "2_2") (pintype "passive"))
      (node (ref "C37") (pin "2") (pinfunction "2_2") (pintype "passive"))
      (node (ref "C38") (pin "2") (pinfunction "2_2") (pintype "passive"))
      (node (ref "C39") (pin "2") (pinfunction "2_2") (pintype "passive"))
      (node (ref "C4") (pin "2") (pinfunction "2_2") (pintype "passive"))
      (node (ref "C40") (pin "2") (pinfunction "2_2") (pintype "passive"))
      (node (ref "C41") (pin "2") (pinfunction "2_2") (pintype "passive"))
      (node (ref "C42") (pin "1") (pinfunction "1_1") (pintype "passive"))
      (node (ref "C43") (pin "1") (pinfunction "1_1") (pintype "passive"))
      (node (ref "C5") (pin "2") (pinfunction "2_2") (pintype "passive"))
      (node (ref "C6") (pin "2") (pinfunction "2_2") (pintype "passive"))
      (node (ref "C69") (pin "2") (pinfunction "2_2") (pintype "passive"))
      (node (ref "C7") (pin "2") (pinfunction "2_2") (pintype "passive"))
      (node (ref "C70") (pin "2") (pinfunction "2_2") (pintype "passive"))
      (node (ref "C8") (pin "2") (pinfunction "2_2") (pintype "passive"))
      (node (ref "C9") (pin "2") (pinfunction "2_2") (pintype "passive"))
      (node (ref "E2") (pin "GND") (pinfunction "GND_GND") (pintype "bidirectional"))
      (node (ref "E2") (pin "GND2") (pinfunction "GND_GND2") (pintype "bidirectional"))
      (node (ref "IC1") (pin "5") (pinfunction "+VS_5") (pintype "input"))
      (node (ref "IC2") (pin "11") (pinfunction "V-_11") (pintype "power_in"))
      (node (ref "IC3") (pin "11") (pinfunction "V-_11") (pintype "power_in"))
      (node (ref "IC4") (pin "11") (pinfunction "V-_11") (pintype "power_in"))
      (node (ref "IC5") (pin "5") (pinfunction "+VS_5") (pintype "input"))
      (node (ref "IC6") (pin "5") (pinfunction "+VS_5") (pintype "input"))
      (node (ref "JP1") (pin "5") (pinfunction "GND_5") (pintype "bidirectional"))
      (node (ref "JP1") (pin "P$5") (pinfunction "GND1_P$5") (pintype "bidirectional"))
      (node (ref "JP1") (pin "P$6") (pinfunction "GND2_P$6") (pintype "bidirectional"))
      (node (ref "JP2") (pin "1") (pinfunction "1_1") (pintype "passive"))
      (node (ref "JP3") (pin "11") (pinfunction "L_11") (pintype "bidirectional"))
      (node (ref "JP4") (pin "11") (pinfunction "L_11") (pintype "bidirectional"))
      (node (ref "JP5") (pin "11") (pinfunction "L_11") (pintype "bidirectional"))
      (node (ref "L3") (pin "2") (pinfunction "2_2") (pintype "passive"))
      (node (ref "LED2") (pin "3-GND") (pinfunction "GND_3-GND") (pintype "power_in"))
      (node (ref "PAD3") (pin "1") (pinfunction "P_1") (pintype "passive"))
      (node (ref "R2") (pin "1") (pinfunction "1_1") (pintype "passive"))
      (node (ref "R7") (pin "2") (pinfunction "2_2") (pintype "passive"))
      (node (ref "R9") (pin "2") (pinfunction "2_2") (pintype "passive"))
      (node (ref "RN1") (pin "6") (pinfunction "2_6") (pintype "passive"))
      (node (ref "RN2") (pin "2") (pinfunction "1_2") (pintype "passive"))
      (node (ref "RN2") (pin "4") (pinfunction "1_4") (pintype "passive"))
      (node (ref "RN3") (pin "5") (pinfunction "2_5") (pintype "passive"))
      (node (ref "RN4") (pin "3") (pinfunction "2_3") (pintype "passive"))
      (node (ref "RN5") (pin "3") (pinfunction "2_3") (pintype "passive"))
      (node (ref "S1") (pin "1") (pinfunction "O_1") (pintype "passive"))
      (node (ref "U1") (pin "2") (pinfunction "VSS_2") (pintype "power_in"))
      (node (ref "U10") (pin "EP") (pinfunction "GND_EP") (pintype "bidirectional"))
      (node (ref "U11") (pin "4") (pinfunction "GND_4") (pintype "bidirectional"))
      (node (ref "U2") (pin "1") (pinfunction "RESERVED_1") (pintype "bidirectional"))
      (node (ref "U2") (pin "4") (pinfunction "AVSS_4") (pintype "bidirectional"))
      (node (ref "U2") (pin "8") (pinfunction "DVSS_8") (pintype "bidirectional"))
      (node (ref "U3") (pin "2") (pinfunction "GND_2") (pintype "input"))
      (node (ref "U6") (pin "4") (pinfunction "GND_4") (pintype "bidirectional"))
      (node (ref "U7") (pin "2") (pinfunction "GND_2") (pintype "power_in"))
      (node (ref "U8") (pin "2") (pinfunction "GND_2") (pintype "input"))
      (node (ref "Y2") (pin "2") (pinfunction "GND_2") (pintype "passive"))
      (node (ref "Y2") (pin "4") (pinfunction "GND_4") (pintype "passive"))
    )
    (net (code "34") (name "I2C_SCL") (class "Default")
      (node (ref "U10") (pin "39") (pinfunction "(VSPIWP/HS2_CLK)GPIO22_39") (pintype "bidirectional"))
      (node (ref "U11") (pin "2") (pinfunction "SCL_2") (pintype "bidirectional"))
      (node (ref "U2") (pin "6") (pinfunction "SCL_6") (pintype "bidirectional"))
    )
    (net (code "35") (name "I2C_SDA") (class "Default")
      (node (ref "U10") (pin "42") (pinfunction "(VSPIHD/HS2_CMD)GPIO21_42") (pintype "bidirectional"))
      (node (ref "U11") (pin "1") (pinfunction "SDA_1") (pintype "bidirectional"))
      (node (ref "U2") (pin "7") (pinfunction "SDA_7") (pintype "bidirectional"))
    )
    (net (code "36") (name "INT") (class "Default")
      (node (ref "INT") (pin "P$1") (pinfunction "1_P$1") (pintype "bidirectional"))
      (node (ref "U2") (pin "5") (pinfunction "~{INT}_5") (pintype "bidirectional"))
    )
    (net (code "37") (name "LOOP6") (class "Default")
      (node (ref "IC2") (pin "6") (pinfunction "-IN_6") (pintype "input"))
      (node (ref "IC2") (pin "7") (pinfunction "OUT_7") (pintype "output"))
      (node (ref "RN3") (pin "2") (pinfunction "1_2") (pintype "passive"))
    )
    (net (code "38") (name "LOOP9") (class "Default")
      (node (ref "IC2") (pin "8") (pinfunction "OUT_8") (pintype "output"))
      (node (ref "IC2") (pin "9") (pinfunction "-IN_9") (pintype "input"))
      (node (ref "RN3") (pin "1") (pinfunction "1_1") (pintype "passive"))
    )
    (net (code "39") (name "Net-(C23-Pad1)") (class "Default")
      (node (ref "C23") (pin "1") (pinfunction "1_1") (pintype "passive"))
      (node (ref "R12") (pin "2") (pinfunction "2_2") (pintype "passive"))
      (node (ref "R13") (pin "1") (pinfunction "1_1") (pintype "passive"))
    )
    (net (code "40") (name "Net-(CHG2-PadA)") (class "Default")
      (node (ref "CHG2") (pin "A") (pinfunction "A_A") (pintype "passive"))
      (node (ref "R1") (pin "2") (pinfunction "2_2") (pintype "passive"))
    )
    (net (code "41") (name "Net-(D2A-A)") (class "Default")
      (node (ref "D2") (pin "1") (pinfunction "A_1") (pintype "passive"))
      (node (ref "D2") (pin "4") (pinfunction "C_4") (pintype "passive"))
      (node (ref "D4") (pin "3") (pinfunction "A_3") (pintype "passive"))
      (node (ref "D4") (pin "6") (pinfunction "C_6") (pintype "passive"))
      (node (ref "PAD2") (pin "1") (pinfunction "P_1") (pintype "passive"))
      (node (ref "R3") (pin "2") (pinfunction "1_2") (pintype "passive"))
    )
    (net (code "42") (name "Net-(D2A-C)") (class "Default")
      (node (ref "D2") (pin "3") (pinfunction "A_3") (pintype "passive"))
      (node (ref "D2") (pin "6") (pinfunction "C_6") (pintype "passive"))
      (node (ref "D3") (pin "3") (pinfunction "A_3") (pintype "passive"))
      (node (ref "D3") (pin "6") (pinfunction "C_6") (pintype "passive"))
      (node (ref "PAD1") (pin "1") (pinfunction "P_1") (pintype "passive"))
      (node (ref "R3") (pin "4") (pinfunction "1_4") (pintype "passive"))
    )
    (net (code "43") (name "Net-(D3A-A)") (class "Default")
      (node (ref "D3") (pin "1") (pinfunction "A_1") (pintype "passive"))
      (node (ref "D3") (pin "4") (pinfunction "C_4") (pintype "passive"))
      (node (ref "D4") (pin "1") (pinfunction "A_1") (pintype "passive"))
      (node (ref "D4") (pin "4") (pinfunction "C_4") (pintype "passive"))
      (node (ref "PAD5") (pin "1") (pinfunction "P_1") (pintype "passive"))
      (node (ref "RN1") (pin "8") (pinfunction "2_8") (pintype "passive"))
    )
    (net (code "44") (name "Net-(E2-SIGNAL)") (class "Default")
      (node (ref "C33") (pin "1") (pinfunction "1_1") (pintype "passive"))
      (node (ref "C34") (pin "2") (pinfunction "2_2") (pintype "passive"))
      (node (ref "E2") (pin "ANT") (pinfunction "SIGNAL_ANT") (pintype "bidirectional"))
    )
    (net (code "45") (name "Net-(IC1-IN+)") (class "Default")
      (node (ref "C18") (pin "1") (pinfunction "1_1") (pintype "passive"))
      (node (ref "IC1") (pin "3") (pinfunction "IN+_3") (pintype "input"))
      (node (ref "RN4") (pin "1") (pinfunction "1_1") (pintype "passive"))
      (node (ref "RN4") (pin "2") (pinfunction "1_2") (pintype "passive"))
    )
    (net (code "46") (name "Net-(IC3A-+IN)") (class "Default")
      (node (ref "IC3") (pin "3") (pinfunction "+IN_3") (pintype "input"))
      (node (ref "R3") (pin "13") (pinfunction "2_13") (pintype "passive"))
    )
    (net (code "47") (name "Net-(IC3A--IN)") (class "Default")
      (node (ref "IC3") (pin "2") (pinfunction "-IN_2") (pintype "input"))
      (node (ref "R3") (pin "5") (pinfunction "1_5") (pintype "passive"))
      (node (ref "RN1") (pin "4") (pinfunction "1_4") (pintype "passive"))
    )
    (net (code "48") (name "Net-(IC3A-OUT)") (class "Default")
      (node (ref "IC3") (pin "1") (pinfunction "OUT_1") (pintype "output"))
      (node (ref "R3") (pin "12") (pinfunction "2_12") (pintype "passive"))
      (node (ref "R3") (pin "8") (pinfunction "1_8") (pintype "passive"))
      (node (ref "R5") (pin "1") (pinfunction "1_1") (pintype "passive"))
    )
    (net (code "49") (name "Net-(IC3B-+IN)") (class "Default")
      (node (ref "IC3") (pin "5") (pinfunction "+IN_5") (pintype "input"))
      (node (ref "R3") (pin "15") (pinfunction "2_15") (pintype "passive"))
    )
    (net (code "50") (name "Net-(IC3B--IN)") (class "Default")
      (node (ref "IC3") (pin "6") (pinfunction "-IN_6") (pintype "input"))
      (node (ref "R3") (pin "16") (pinfunction "2_16") (pintype "passive"))
      (node (ref "RN1") (pin "5") (pinfunction "2_5") (pintype "passive"))
    )
    (net (code "51") (name "Net-(IC3B-OUT)") (class "Default")
      (node (ref "IC3") (pin "7") (pinfunction "OUT_7") (pintype "output"))
      (node (ref "R3") (pin "1") (pinfunction "1_1") (pintype "passive"))
      (node (ref "R3") (pin "14") (pinfunction "2_14") (pintype "passive"))
    )
    (net (code "52") (name "Net-(IC3C-+IN)") (class "Default")
      (node (ref "IC3") (pin "10") (pinfunction "+IN_10") (pintype "input"))
      (node (ref "RN1") (pin "3") (pinfunction "1_3") (pintype "passive"))
      (node (ref "RN1") (pin "7") (pinfunction "2_7") (pintype "passive"))
    )
    (net (code "53") (name "Net-(IC3C--IN)") (class "Default")
      (node (ref "IC3") (pin "12") (pinfunction "+IN_12") (pintype "input"))
      (node (ref "IC3") (pin "8") (pinfunction "OUT_8") (pintype "output"))
      (node (ref "IC3") (pin "9") (pinfunction "-IN_9") (pintype "input"))
      (node (ref "IC4") (pin "10") (pinfunction "+IN_10") (pintype "input"))
      (node (ref "RN1") (pin "1") (pinfunction "1_1") (pintype "passive"))
      (node (ref "RN7") (pin "1") (pinfunction "1_1") (pintype "passive"))
    )
    (net (code "54") (name "Net-(IC3D--IN)") (class "Default")
      (node (ref "IC3") (pin "13") (pinfunction "-IN_13") (pintype "input"))
      (node (ref "R3") (pin "10") (pinfunction "2_10") (pintype "passive"))
      (node (ref "R4") (pin "1") (pinfunction "1_1") (pintype "passive"))
      (node (ref "R5") (pin "2") (pinfunction "2_2") (pintype "passive"))
    )
    (net (code "55") (name "Net-(IC4B-+IN)") (class "Default")
      (node (ref "C14") (pin "1") (pinfunction "1_1") (pintype "passive"))
      (node (ref "IC4") (pin "5") (pinfunction "+IN_5") (pintype "input"))
      (node (ref "R3") (pin "9") (pinfunction "2_9") (pintype "passive"))
      (node (ref "RN7") (pin "4") (pinfunction "1_4") (pintype "passive"))
    )
    (net (code "56") (name "Net-(IC4B--IN)") (class "Default")
      (node (ref "C13") (pin "1") (pinfunction "1_1") (pintype "passive"))
      (node (ref "IC4") (pin "6") (pinfunction "-IN_6") (pintype "input"))
      (node (ref "RN7") (pin "8") (pinfunction "2_8") (pintype "passive"))
    )
    (net (code "57") (name "Net-(IC4B-OUT)") (class "Default")
      (node (ref "C13") (pin "2") (pinfunction "2_2") (pintype "passive"))
      (node (ref "IC4") (pin "7") (pinfunction "OUT_7") (pintype "output"))
      (node (ref "RN7") (pin "7") (pinfunction "2_7") (pintype "passive"))
    )
    (net (code "58") (name "Net-(IC4C--IN)") (class "Default")
      (node (ref "IC4") (pin "9") (pinfunction "-IN_9") (pintype "input"))
      (node (ref "R3") (pin "3") (pinfunction "1_3") (pintype "passive"))
      (node (ref "RN7") (pin "2") (pinfunction "1_2") (pintype "passive"))
      (node (ref "RN7") (pin "6") (pinfunction "2_6") (pintype "passive"))
    )
    (net (code "59") (name "Net-(IC4C-OUT)") (class "Default")
      (node (ref "IC4") (pin "8") (pinfunction "OUT_8") (pintype "output"))
      (node (ref "R4") (pin "2") (pinfunction "2_2") (pintype "passive"))
      (node (ref "RN7") (pin "3") (pinfunction "1_3") (pintype "passive"))
      (node (ref "RN7") (pin "5") (pinfunction "2_5") (pintype "passive"))
    )
    (net (code "60") (name "Net-(IC5-IN-)") (class "Default")
      (node (ref "IC5") (pin "4") (pinfunction "IN-_4") (pintype "input"))
      (node (ref "LSP1") (pin "MP") (pinfunction "MP_MP") (pintype "passive"))
      (node (ref "R11") (pin "2") (pinfunction "2_2") (pintype "passive"))
    )
    (net (code "61") (name "Net-(IC6-IN+)") (class "Default")
      (node (ref "C22") (pin "1") (pinfunction "1_1") (pintype "passive"))
      (node (ref "IC6") (pin "3") (pinfunction "IN+_3") (pintype "input"))
      (node (ref "R13") (pin "2") (pinfunction "2_2") (pintype "passive"))
    )
    (net (code "62") (name "Net-(IC6-IN-)") (class "Default")
      (node (ref "C24") (pin "1") (pinfunction "1_1") (pintype "passive"))
      (node (ref "IC6") (pin "4") (pinfunction "IN-_4") (pintype "input"))
      (node (ref "RN5") (pin "1") (pinfunction "1_1") (pintype "passive"))
    )
    (net (code "63") (name "Net-(IC6-OUT)") (class "Default")
      (node (ref "C23") (pin "2") (pinfunction "2_2") (pintype "passive"))
      (node (ref "C24") (pin "2") (pinfunction "2_2") (pintype "passive"))
      (node (ref "IC6") (pin "1") (pinfunction "OUT_1") (pintype "output"))
      (node (ref "R14") (pin "1") (pinfunction "1_1") (pintype "passive"))
      (node (ref "RN5") (pin "2") (pinfunction "1_2") (pintype "passive"))
      (node (ref "RN5") (pin "4") (pinfunction "2_4") (pintype "passive"))
    )
    (net (code "64") (name "Net-(JP3-R)") (class "Default")
      (node (ref "JP3") (pin "00") (pinfunction "R_00") (pintype "bidirectional"))
      (node (ref "JP4") (pin "00") (pinfunction "R_00") (pintype "bidirectional"))
      (node (ref "JP5") (pin "00") (pinfunction "R_00") (pintype "bidirectional"))
      (node (ref "R8") (pin "2") (pinfunction "2_2") (pintype "passive"))
    )
    (net (code "65") (name "Net-(LED2-DI)") (class "Default")
      (node (ref "LED2") (pin "4-DIN") (pinfunction "DI_4-DIN") (pintype "input"))
      (node (ref "R6") (pin "2") (pinfunction "2_2") (pintype "passive"))
    )
    (net (code "66") (name "Net-(Q2A-B)") (class "Default")
      (node (ref "Q2") (pin "5") (pinfunction "B_5") (pintype "passive"))
      (node (ref "RN8") (pin "3") (pinfunction "1_3") (pintype "passive"))
    )
    (net (code "67") (name "Net-(Q2B-B)") (class "Default")
      (node (ref "Q2") (pin "2") (pinfunction "B_2") (pintype "passive"))
      (node (ref "RN8") (pin "4") (pinfunction "1_4") (pintype "passive"))
    )
    (net (code "68") (name "Net-(R3F-2)") (class "Default")
      (node (ref "R3") (pin "11") (pinfunction "2_11") (pintype "passive"))
      (node (ref "R3") (pin "7") (pinfunction "1_7") (pintype "passive"))
    )
    (net (code "69") (name "Net-(U1-PROG)") (class "Default")
      (node (ref "R2") (pin "2") (pinfunction "2_2") (pintype "passive"))
      (node (ref "U1") (pin "5") (pinfunction "PROG_5") (pintype "input"))
    )
    (net (code "70") (name "Net-(U1-STAT)") (class "Default")
      (node (ref "CHG2") (pin "C") (pinfunction "C_C") (pintype "passive"))
      (node (ref "U1") (pin "1") (pinfunction "STAT_1") (pintype "output"))
    )
    (net (code "71") (name "Net-(U7A-TXD)") (class "Default")
      (node (ref "R32") (pin "1") (pinfunction "1_1") (pintype "passive"))
      (node (ref "U7") (pin "21") (pinfunction "TXD_21") (pintype "output"))
    )
    (net (code "72") (name "Net-(U7A-VPP)") (class "Default")
      (node (ref "C70") (pin "1") (pinfunction "1_1") (pintype "passive"))
      (node (ref "U7") (pin "16") (pinfunction "VPP_16") (pintype "bidirectional"))
    )
    (net (code "73") (name "Net-(U10-CAP1)") (class "Default")
      (node (ref "C31") (pin "2") (pinfunction "2_2") (pintype "passive"))
      (node (ref "C44") (pin "1") (pinfunction "1_1") (pintype "passive"))
      (node (ref "R22") (pin "2") (pinfunction "2_2") (pintype "passive"))
      (node (ref "U10") (pin "48") (pinfunction "CAP1_48") (pintype "bidirectional"))
    )
    (net (code "74") (name "Net-(U10-CAP2)") (class "Default")
      (node (ref "C44") (pin "2") (pinfunction "2_2") (pintype "passive"))
      (node (ref "R22") (pin "1") (pinfunction "1_1") (pintype "passive"))
      (node (ref "U10") (pin "47") (pinfunction "CAP2_47") (pintype "bidirectional"))
    )
    (net (code "75") (name "Net-(U10-LNA_IN)") (class "Default")
      (node (ref "C34") (pin "1") (pinfunction "1_1") (pintype "passive"))
      (node (ref "L3") (pin "1") (pinfunction "1_1") (pintype "passive"))
      (node (ref "U10") (pin "2") (pinfunction "LNA_IN_2") (pintype "bidirectional"))
    )
    (net (code "76") (name "Net-(U10-XTAL_N)") (class "Default")
      (node (ref "C28") (pin "2") (pinfunction "2_2") (pintype "passive"))
      (node (ref "U10") (pin "44") (pinfunction "XTAL_N_44") (pintype "bidirectional"))
      (node (ref "Y2") (pin "3") (pinfunction "2_3") (pintype "passive"))
    )
    (net (code "77") (name "Net-(U10-XTAL_P)") (class "Default")
      (node (ref "C27") (pin "2") (pinfunction "2_2") (pintype "passive"))
      (node (ref "U10") (pin "45") (pinfunction "XTAL_P_45") (pintype "bidirectional"))
      (node (ref "Y2") (pin "1") (pinfunction "1_1") (pintype "passive"))
    )
    (net (code "78") (name "PAD+") (class "Default")
      (node (ref "C1") (pin "2") (pinfunction "2_2") (pintype "passive"))
      (node (ref "IC2") (pin "10") (pinfunction "+IN_10") (pintype "input"))
      (node (ref "PAD4") (pin "1") (pinfunction "P_1") (pintype "passive"))
      (node (ref "RN2") (pin "1") (pinfunction "1_1") (pintype "passive"))
      (node (ref "RN2") (pin "7") (pinfunction "2_7") (pintype "passive"))
    )
    (net (code "79") (name "RTS") (class "Default")
      (node (ref "Q2") (pin "4") (pinfunction "E_4") (pintype "passive"))
      (node (ref "RN8") (pin "5") (pinfunction "2_5") (pintype "passive"))
      (node (ref "U7") (pin "19") (pinfunction "RTS_19") (pintype "output"))
    )
    (net (code "80") (name "SENSE_OUT") (class "Default")
      (node (ref "IC2") (pin "1") (pinfunction "OUT_1") (pintype "output"))
      (node (ref "RN3") (pin "3") (pinfunction "1_3") (pintype "passive"))
      (node (ref "TP2") (pin "TP") (pinfunction "TP_TP") (pintype "input"))
      (node (ref "U10") (pin "24") (pinfunction "(ADC2:0/TOUCH0/RTC10/SPIHD)GPIO4_24") (pintype "bidirectional"))
    )
    (net (code "81") (name "U0RXD") (class "Default")
      (node (ref "R32") (pin "2") (pinfunction "2_2") (pintype "passive"))
      (node (ref "U10") (pin "40") (pinfunction "(GPIO3/CLK_OUT2/HS2_DATA0)U0RXD_40") (pintype "bidirectional"))
    )
    (net (code "82") (name "U0TXD") (class "Default")
      (node (ref "U10") (pin "41") (pinfunction "(GPIO1/CLK_OUT3/HS2_DATA1)U0TXD_41") (pintype "bidirectional"))
      (node (ref "U7") (pin "20") (pinfunction "RXD_20") (pintype "input"))
    )
    (net (code "83") (name "USBD+") (class "Default")
      (node (ref "JP1") (pin "3") (pinfunction "D+_3") (pintype "bidirectional"))
      (node (ref "U7") (pin "3") (pinfunction "D+_3") (pintype "bidirectional"))
    )
    (net (code "84") (name "USBD-") (class "Default")
      (node (ref "JP1") (pin "2") (pinfunction "D-_2") (pintype "bidirectional"))
      (node (ref "U7") (pin "4") (pinfunction "D-_4") (pintype "bidirectional"))
    )
    (net (code "85") (name "VBAT") (class "Default")
      (node (ref "C6") (pin "1") (pinfunction "1_1") (pintype "passive"))
      (node (ref "JP2") (pin "2") (pinfunction "2_2") (pintype "passive"))
      (node (ref "Q1") (pin "3") (pinfunction "D_3") (pintype "passive"))
      (node (ref "R10") (pin "1") (pinfunction "1_1") (pintype "passive"))
      (node (ref "U1") (pin "3") (pinfunction "VBAT_3") (pintype "power_in"))
    )
    (net (code "86") (name "VCC") (class "Default")
      (node (ref "C19") (pin "1") (pinfunction "1_1") (pintype "passive"))
      (node (ref "C19") (pin "2") (pinfunction "2_2") (pintype "passive"))
      (node (ref "C20") (pin "1") (pinfunction "1_1") (pintype "passive"))
      (node (ref "C21") (pin "1") (pinfunction "1_1") (pintype "passive"))
      (node (ref "IC1") (pin "1") (pinfunction "OUT_1") (pintype "output"))
      (node (ref "IC1") (pin "2") (pinfunction "-VS_2") (pintype "input"))
      (node (ref "IC1") (pin "4") (pinfunction "IN-_4") (pintype "input"))
      (node (ref "IC5") (pin "1") (pinfunction "OUT_1") (pintype "output"))
      (node (ref "IC5") (pin "2") (pinfunction "-VS_2") (pintype "input"))
      (node (ref "IC5") (pin "3") (pinfunction "IN+_3") (pintype "input"))
      (node (ref "IC6") (pin "2") (pinfunction "-VS_2") (pintype "input"))
      (node (ref "LSP2") (pin "MP") (pinfunction "MP_MP") (pintype "passive"))
      (node (ref "R11") (pin "1") (pinfunction "1_1") (pintype "passive"))
      (node (ref "R12") (pin "1") (pinfunction "1_1") (pintype "passive"))
      (node (ref "RN4") (pin "4") (pinfunction "2_4") (pintype "passive"))
    )
    (net (code "87") (name "VIN") (class "Default")
      (node (ref "C11") (pin "2") (pinfunction "2_2") (pintype "passive"))
      (node (ref "C2") (pin "1") (pinfunction "1_1") (pintype "passive"))
      (node (ref "C7") (pin "1") (pinfunction "1_1") (pintype "passive"))
      (node (ref "D1") (pin "C") (pinfunction "C_C") (pintype "passive"))
      (node (ref "Q1") (pin "2") (pinfunction "S_2") (pintype "passive"))
      (node (ref "S1") (pin "3") (pinfunction "S_3") (pintype "passive"))
      (node (ref "U3") (pin "1") (pinfunction "IN_1") (pintype "input"))
      (node (ref "U8") (pin "1") (pinfunction "IN_1") (pintype "input"))
    )
    (net (code "88") (name "VOLTAG_DEV") (class "Default")
      (node (ref "IC2") (pin "5") (pinfunction "+IN_5") (pintype "input"))
      (node (ref "RN2") (pin "3") (pinfunction "1_3") (pintype "passive"))
      (node (ref "RN2") (pin "5") (pinfunction "2_5") (pintype "passive"))
    )
    (net (code "89") (name "VUSB") (class "Default")
      (node (ref "C17") (pin "1") (pinfunction "1_1") (pintype "passive"))
      (node (ref "C3") (pin "1") (pinfunction "1_1") (pintype "passive"))
      (node (ref "D1") (pin "A") (pinfunction "A_A") (pintype "passive"))
      (node (ref "JP1") (pin "1") (pinfunction "VCC_1") (pintype "bidirectional"))
      (node (ref "Q1") (pin "1") (pinfunction "G_1") (pintype "passive"))
      (node (ref "R1") (pin "1") (pinfunction "1_1") (pintype "passive"))
      (node (ref "R7") (pin "1") (pinfunction "1_1") (pintype "passive"))
      (node (ref "U1") (pin "4") (pinfunction "VIN_4") (pintype "power_in"))
      (node (ref "U7") (pin "8") (pinfunction "VBUS_8") (pintype "power_in"))
    )
    (net (code "90") (name "WS2812{slash}GPIO14") (class "Default")
      (node (ref "R6") (pin "1") (pinfunction "1_1") (pintype "passive"))
      (node (ref "U10") (pin "17") (pinfunction "(GPIO14/ADC2:6/TOUCH6/RTC16/SPICLK)MTMS_17") (pintype "bidirectional"))
    )
    (net (code "91") (name "unconnected-(JP1-ID-Pad4)") (class "Default")
      (node (ref "JP1") (pin "4") (pinfunction "ID_4") (pintype "bidirectional"))
    )
    (net (code "92") (name "unconnected-(LED2-DO-Pad2-DOUT)") (class "Default")
      (node (ref "LED2") (pin "2-DOUT") (pinfunction "DO_2-DOUT") (pintype "output"))
    )
    (net (code "93") (name "unconnected-(U2-NC0-Pad2)") (class "Default")
      (node (ref "U2") (pin "2") (pinfunction "NC0_2") (pintype "bidirectional"))
    )
    (net (code "94") (name "unconnected-(U2-NC1-Pad11)") (class "Default")
      (node (ref "U2") (pin "11") (pinfunction "NC1_11") (pintype "bidirectional"))
    )
    (net (code "95") (name "unconnected-(U2-NC2-Pad10)") (class "Default")
      (node (ref "U2") (pin "10") (pinfunction "NC2_10") (pintype "bidirectional"))
    )
    (net (code "96") (name "unconnected-(U2-NC3-Pad12)") (class "Default")
      (node (ref "U2") (pin "12") (pinfunction "NC3_12") (pintype "bidirectional"))
    )
    (net (code "97") (name "unconnected-(U3-BP-Pad4)") (class "Default")
      (node (ref "U3") (pin "4") (pinfunction "BP_4") (pintype "input"))
    )
    (net (code "98") (name "unconnected-(U7A-#RST-Pad9)") (class "Default")
      (node (ref "U7") (pin "9") (pinfunction "#RST_9") (pintype "bidirectional"))
    )
    (net (code "99") (name "unconnected-(U7A-#SUSPEND-Pad15)") (class "Default")
      (node (ref "U7") (pin "15") (pinfunction "#SUSPEND_15") (pintype "output"))
    )
    (net (code "100") (name "unconnected-(U7A-CTS-Pad18)") (class "Default")
      (node (ref "U7") (pin "18") (pinfunction "CTS_18") (pintype "input"))
    )
    (net (code "101") (name "unconnected-(U7A-DCD-Pad24)") (class "Default")
      (node (ref "U7") (pin "24") (pinfunction "DCD_24") (pintype "input"))
    )
    (net (code "102") (name "unconnected-(U7A-DSR-Pad22)") (class "Default")
      (node (ref "U7") (pin "22") (pinfunction "DSR_22") (pintype "input"))
    )
    (net (code "103") (name "unconnected-(U7A-GPIO0{slash}TXLED-Pad14)") (class "Default")
      (node (ref "U7") (pin "14") (pinfunction "GPIO0/TXLED_14") (pintype "bidirectional"))
    )
    (net (code "104") (name "unconnected-(U7A-GPIO1{slash}RXLED-Pad13)") (class "Default")
      (node (ref "U7") (pin "13") (pinfunction "GPIO1/RXLED_13") (pintype "bidirectional"))
    )
    (net (code "105") (name "unconnected-(U7A-GPIO2-Pad12)") (class "Default")
      (node (ref "U7") (pin "12") (pinfunction "GPIO2_12") (pintype "bidirectional"))
    )
    (net (code "106") (name "unconnected-(U7A-GPIO3-Pad11)") (class "Default")
      (node (ref "U7") (pin "11") (pinfunction "GPIO3_11") (pintype "bidirectional"))
    )
    (net (code "107") (name "unconnected-(U7A-NC-Pad10)") (class "Default")
      (node (ref "U7") (pin "10") (pinfunction "NC_10") (pintype "no_connect"))
    )
    (net (code "108") (name "unconnected-(U7A-RI-Pad1)") (class "Default")
      (node (ref "U7") (pin "1") (pinfunction "RI_1") (pintype "input"))
    )
    (net (code "109") (name "unconnected-(U7A-SUSPEND-Pad17)") (class "Default")
      (node (ref "U7") (pin "17") (pinfunction "SUSPEND_17") (pintype "output"))
    )
    (net (code "110") (name "unconnected-(U8-BP-Pad4)") (class "Default")
      (node (ref "U8") (pin "4") (pinfunction "BP_4") (pintype "input"))
    )
    (net (code "111") (name "unconnected-(U10-(ADC2:2{slash}TOUCH2{slash}RTC12{slash}SPIWP)GPIO2-Pad22)") (class "Default")
      (node (ref "U10") (pin "22") (pinfunction "(ADC2:2/TOUCH2/RTC12/SPIWP)GPIO2_22") (pintype "bidirectional"))
    )
    (net (code "112") (name "unconnected-(U10-(GPIO12{slash}ADC2:5{slash}TOUCH5{slash}RTC15{slash}SPIQ)MTDI-Pad18)") (class "Default")
      (node (ref "U10") (pin "18") (pinfunction "(GPIO12/ADC2:5/TOUCH5/RTC15/SPIQ)MTDI_18") (pintype "bidirectional"))
    )
    (net (code "113") (name "unconnected-(U10-(GPIO15{slash}ADC2:3{slash}TOUCH3{slash}RTC13{slash}SPICSO{slash}U0RTS)MTDO-Pad21)") (class "Default")
      (node (ref "U10") (pin "21") (pinfunction "(GPIO15/ADC2:3/TOUCH3/RTC13/SPICSO/U0RTS)MTDO_21") (pintype "bidirectional"))
    )
    (net (code "114") (name "unconnected-(U10-(HS1_DATA4)GPIO16-Pad25)") (class "Default")
      (node (ref "U10") (pin "25") (pinfunction "(HS1_DATA4)GPIO16_25") (pintype "bidirectional"))
    )
    (net (code "115") (name "unconnected-(U10-(HS1_DATA5)GPIO17-Pad27)") (class "Default")
      (node (ref "U10") (pin "27") (pinfunction "(HS1_DATA5)GPIO17_27") (pintype "bidirectional"))
    )
    (net (code "116") (name "unconnected-(U10-(VSPICS0{slash}HS1_DATA6)GPIO5-Pad34)") (class "Default")
      (node (ref "U10") (pin "34") (pinfunction "(VSPICS0/HS1_DATA6)GPIO5_34") (pintype "bidirectional"))
    )
    (net (code "117") (name "unconnected-(U10-SENSOR_CAPP(GPI37{slash}ADC1:1{slash}RTC1)-Pad6)") (class "Default")
      (node (ref "U10") (pin "6") (pinfunction "SENSOR_CAPP(GPI37/ADC1:1/RTC1)_6") (pintype "bidirectional"))
    )
    (net (code "118") (name "unconnected-(U10-VDET_1(GPI34{slash}ADC1:6)-Pad10)") (class "Default")
      (node (ref "U10") (pin "10") (pinfunction "VDET_1(GPI34/ADC1:6)_10") (pintype "bidirectional"))
    )
    (net (code "119") (name "unconnected-(U10-VDET_2(GPI35{slash}ADC1:7)-Pad11)") (class "Default")
      (node (ref "U10") (pin "11") (pinfunction "VDET_2(GPI35/ADC1:7)_11") (pintype "bidirectional"))
    )
    (net (code "120") (name "~{ALERT}") (class "Default")
      (node (ref "GND16") (pin "T") (pinfunction "T_T") (pintype "bidirectional"))
      (node (ref "R15") (pin "1") (pinfunction "1_1") (pintype "passive"))
      (node (ref "U11") (pin "3") (pinfunction "ALERT_3") (pintype "bidirectional"))
    )
  )
)
